# Rev1.net
KiCad netlist of a schematic drawn in EAGLE
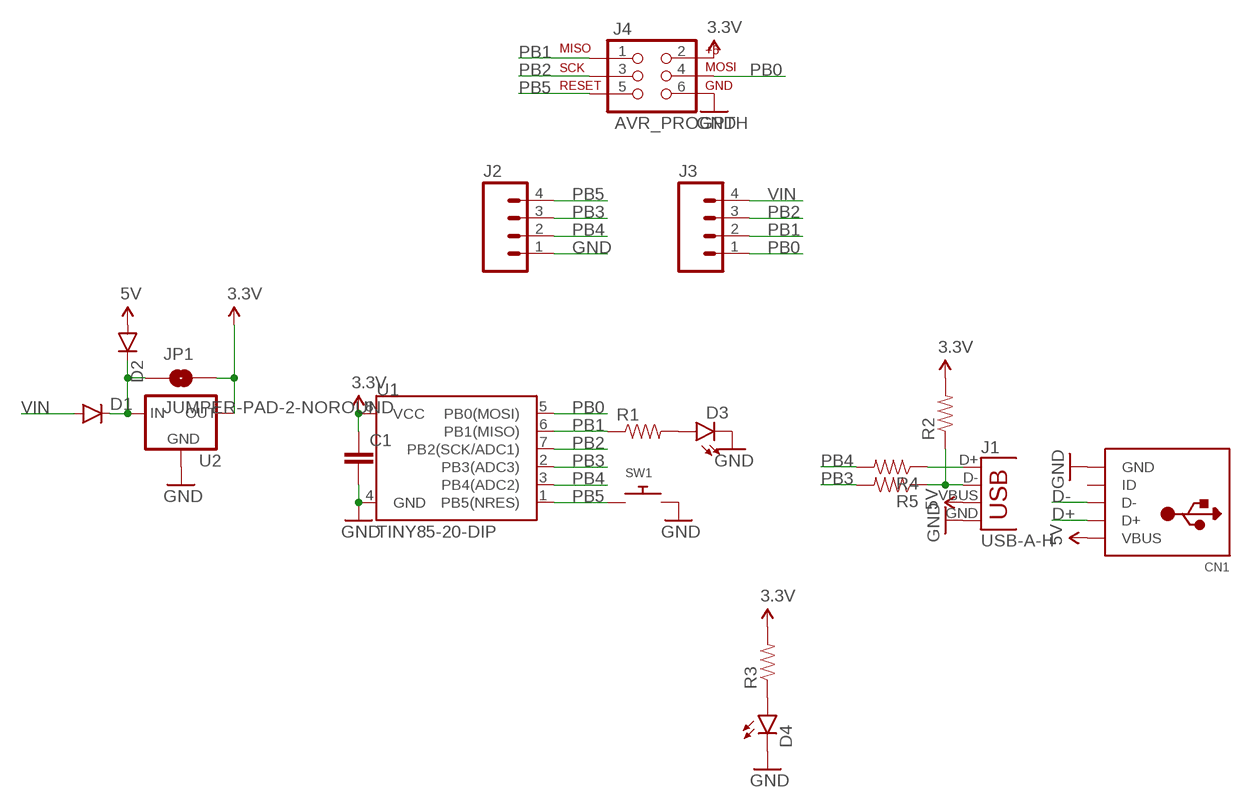
[diagram p0: schematic, sheet 1]

(export (version "E")
  (design (tool "Eeschema 10.0.6"))
  (components
    (comp (ref "C1")
      (value "0.1UF-50V-20%(PTH)KIT-EZ")
      (footprint "eagle-import:CAP-PTH-SMALL-KIT")
      (libsource (lib "eagle-import") (part "0.1UF-50V-20%(PTH)KIT-EZ"))
    )
    (comp (ref "CN1")
      (value "USBTHM")
      (footprint "eagle-import:USB-MINIB-THM")
      (libsource (lib "eagle-import") (part "USBTHM"))
    )
    (comp (ref "D1")
      (value "DIODEPTH")
      (footprint "eagle-import:DIODE-1N4001")
      (libsource (lib "eagle-import") (part "DIODEPTH"))
    )
    (comp (ref "D2")
      (value "DIODEPTH")
      (footprint "eagle-import:DIODE-1N4001")
      (libsource (lib "eagle-import") (part "DIODEPTH"))
    )
    (comp (ref "D3")
      (value "LED3MM")
      (footprint "eagle-import:LED3MM")
      (libsource (lib "eagle-import") (part "LED3MM"))
    )
    (comp (ref "D4")
      (value "LED3MM")
      (footprint "eagle-import:LED3MM")
      (libsource (lib "eagle-import") (part "LED3MM"))
    )
    (comp (ref "J1")
      (value "USB-A-H")
      (footprint "eagle-import:USB-A-H")
      (libsource (lib "eagle-import") (part "USB-A-H"))
    )
    (comp (ref "J2")
      (value "M04PTH")
      (footprint "eagle-import:1X04")
      (libsource (lib "eagle-import") (part "M04PTH"))
    )
    (comp (ref "J3")
      (value "M04PTH")
      (footprint "eagle-import:1X04")
      (libsource (lib "eagle-import") (part "M04PTH"))
    )
    (comp (ref "J4")
      (value "AVR_PROGPTH")
      (footprint "eagle-import:2X3")
      (libsource (lib "eagle-import") (part "AVR_PROGPTH"))
    )
    (comp (ref "JP1")
      (value "JUMPER-PAD-2-NOROUND")
      (footprint "eagle-import:PAD-JUMPER-2-NO_YES_SILK_ROUND")
      (libsource (lib "eagle-import") (part "JUMPER-PAD-2-NOROUND"))
    )
    (comp (ref "R1")
      (value "RESISTORPTH-1/6W")
      (footprint "eagle-import:1_6W-RES")
      (libsource (lib "eagle-import") (part "RESISTORPTH-1/6W"))
    )
    (comp (ref "R2")
      (value "RESISTORPTH-1/6W")
      (footprint "eagle-import:1_6W-RES")
      (libsource (lib "eagle-import") (part "RESISTORPTH-1/6W"))
    )
    (comp (ref "R3")
      (value "RESISTORPTH-1/6W")
      (footprint "eagle-import:1_6W-RES")
      (libsource (lib "eagle-import") (part "RESISTORPTH-1/6W"))
    )
    (comp (ref "R4")
      (value "RESISTORPTH-1/6W")
      (footprint "eagle-import:1_6W-RES")
      (libsource (lib "eagle-import") (part "RESISTORPTH-1/6W"))
    )
    (comp (ref "R5")
      (value "RESISTORPTH-1/6W")
      (footprint "eagle-import:1_6W-RES")
      (libsource (lib "eagle-import") (part "RESISTORPTH-1/6W"))
    )
    (comp (ref "SW1")
      (value "SWITCH_PUSHBUTTONEVQ-PE")
      (footprint "eagle-import:TACT_PANA-EVQ")
      (libsource (lib "eagle-import") (part "SWITCH_PUSHBUTTONEVQ-PE"))
    )
    (comp (ref "U1")
      (value "TINY85-20-DIP")
      (footprint "eagle-import:DIP08")
      (libsource (lib "eagle-import") (part "ATTINY45TINY85-20-DIP"))
    )
    (comp (ref "U2")
      (value "V_REG_78XXTO-92_UNTESTED")
      (footprint "eagle-import:TO-92")
      (libsource (lib "eagle-import") (part "V_REG_78XXTO-92_UNTESTED"))
    )
  )
  (nets
    (net (code "1") (name "/D+") (class "Default")
      (node (ref "CN1") (pin "D+") (pinfunction "D+_D+") (pintype "bidirectional"))
      (node (ref "J1") (pin "D+") (pinfunction "D+_D+") (pintype "bidirectional"))
      (node (ref "R4") (pin "1") (pinfunction "1_1") (pintype "passive"))
    )
    (net (code "2") (name "/D-") (class "Default")
      (node (ref "CN1") (pin "D-") (pinfunction "D-_D-") (pintype "bidirectional"))
      (node (ref "J1") (pin "D-") (pinfunction "D-_D-") (pintype "bidirectional"))
      (node (ref "R2") (pin "1") (pinfunction "1_1") (pintype "passive"))
      (node (ref "R5") (pin "1") (pinfunction "1_1") (pintype "passive"))
    )
    (net (code "3") (name "/PB0") (class "Default")
      (node (ref "J3") (pin "1") (pinfunction "1_1") (pintype "passive"))
      (node (ref "J4") (pin "4") (pinfunction "MOSI_4") (pintype "passive"))
      (node (ref "U1") (pin "5") (pinfunction "PB0(MOSI)_5") (pintype "bidirectional"))
    )
    (net (code "4") (name "/PB1") (class "Default")
      (node (ref "J3") (pin "2") (pinfunction "2_2") (pintype "passive"))
      (node (ref "J4") (pin "1") (pinfunction "MISO_1") (pintype "passive"))
      (node (ref "R1") (pin "1") (pinfunction "1_1") (pintype "passive"))
      (node (ref "U1") (pin "6") (pinfunction "PB1(MISO)_6") (pintype "bidirectional"))
    )
    (net (code "5") (name "/PB2") (class "Default")
      (node (ref "J3") (pin "3") (pinfunction "3_3") (pintype "passive"))
      (node (ref "J4") (pin "3") (pinfunction "SCK_3") (pintype "passive"))
      (node (ref "U1") (pin "7") (pinfunction "PB2(SCK/ADC1)_7") (pintype "bidirectional"))
    )
    (net (code "6") (name "/PB3") (class "Default")
      (node (ref "J2") (pin "3") (pinfunction "3_3") (pintype "passive"))
      (node (ref "R5") (pin "2") (pinfunction "2_2") (pintype "passive"))
      (node (ref "U1") (pin "2") (pinfunction "PB3(ADC3)_2") (pintype "bidirectional"))
    )
    (net (code "7") (name "/PB4") (class "Default")
      (node (ref "J2") (pin "2") (pinfunction "2_2") (pintype "passive"))
      (node (ref "R4") (pin "2") (pinfunction "2_2") (pintype "passive"))
      (node (ref "U1") (pin "3") (pinfunction "PB4(ADC2)_3") (pintype "bidirectional"))
    )
    (net (code "8") (name "/PB5") (class "Default")
      (node (ref "J2") (pin "4") (pinfunction "4_4") (pintype "passive"))
      (node (ref "J4") (pin "5") (pinfunction "RESET_5") (pintype "passive"))
      (node (ref "SW1") (pin "P$1") (pinfunction "P$1_P$1") (pintype "passive"))
      (node (ref "U1") (pin "1") (pinfunction "PB5(NRES)_1") (pintype "bidirectional"))
    )
    (net (code "9") (name "/VIN") (class "Default")
      (node (ref "D1") (pin "A") (pinfunction "A_A") (pintype "passive"))
      (node (ref "J3") (pin "4") (pinfunction "4_4") (pintype "passive"))
    )
    (net (code "10") (name "3.3V") (class "Default")
      (node (ref "C1") (pin "1") (pinfunction "1_1") (pintype "passive"))
      (node (ref "J4") (pin "2") (pinfunction "VIN_2") (pintype "passive"))
      (node (ref "JP1") (pin "2") (pinfunction "2_2") (pintype "passive"))
      (node (ref "R2") (pin "2") (pinfunction "2_2") (pintype "passive"))
      (node (ref "R3") (pin "2") (pinfunction "2_2") (pintype "passive"))
      (node (ref "U1") (pin "8") (pinfunction "VCC_8") (pintype "bidirectional"))
      (node (ref "U2") (pin "1") (pinfunction "OUT_1") (pintype "passive"))
    )
    (net (code "11") (name "5V") (class "Default")
      (node (ref "CN1") (pin "VBUS") (pinfunction "VBUS_VBUS") (pintype "power_in"))
      (node (ref "D2") (pin "A") (pinfunction "A_A") (pintype "passive"))
      (node (ref "J1") (pin "VBUS") (pinfunction "VBUS_VBUS") (pintype "bidirectional"))
    )
    (net (code "12") (name "GND") (class "Default")
      (node (ref "C1") (pin "2") (pinfunction "2_2") (pintype "passive"))
      (node (ref "CN1") (pin "GND") (pinfunction "GND_GND") (pintype "power_in"))
      (node (ref "D3") (pin "K") (pinfunction "C_K") (pintype "passive"))
      (node (ref "D4") (pin "K") (pinfunction "C_K") (pintype "passive"))
      (node (ref "J1") (pin "GND") (pinfunction "GND_GND") (pintype "bidirectional"))
      (node (ref "J2") (pin "1") (pinfunction "1_1") (pintype "passive"))
      (node (ref "J4") (pin "6") (pinfunction "GND_6") (pintype "passive"))
      (node (ref "SW1") (pin "P$2") (pinfunction "P$2_P$2") (pintype "passive"))
      (node (ref "U1") (pin "4") (pinfunction "GND_4") (pintype "bidirectional"))
      (node (ref "U2") (pin "2") (pinfunction "GND_2") (pintype "input"))
    )
    (net (code "13") (name "Net-(D3-PadA)") (class "Default")
      (node (ref "D3") (pin "A") (pinfunction "A_A") (pintype "passive"))
      (node (ref "R1") (pin "2") (pinfunction "2_2") (pintype "passive"))
    )
    (net (code "14") (name "Net-(D4-PadA)") (class "Default")
      (node (ref "D4") (pin "A") (pinfunction "A_A") (pintype "passive"))
      (node (ref "R3") (pin "1") (pinfunction "1_1") (pintype "passive"))
    )
    (net (code "15") (name "Net-(U2-IN)") (class "Default")
      (node (ref "D1") (pin "C") (pinfunction "C_C") (pintype "passive"))
      (node (ref "D2") (pin "C") (pinfunction "C_C") (pintype "passive"))
      (node (ref "JP1") (pin "1") (pinfunction "1_1") (pintype "passive"))
      (node (ref "U2") (pin "3") (pinfunction "IN_3") (pintype "input"))
    )
    (net (code "16") (name "unconnected-(CN1-PadID)") (class "Default")
      (node (ref "CN1") (pin "ID") (pinfunction "ID_ID") (pintype "bidirectional"))
    )
  )
)
